# Power_3Escon_board_v2.net
KiCad netlist of a schematic drawn in EAGLE
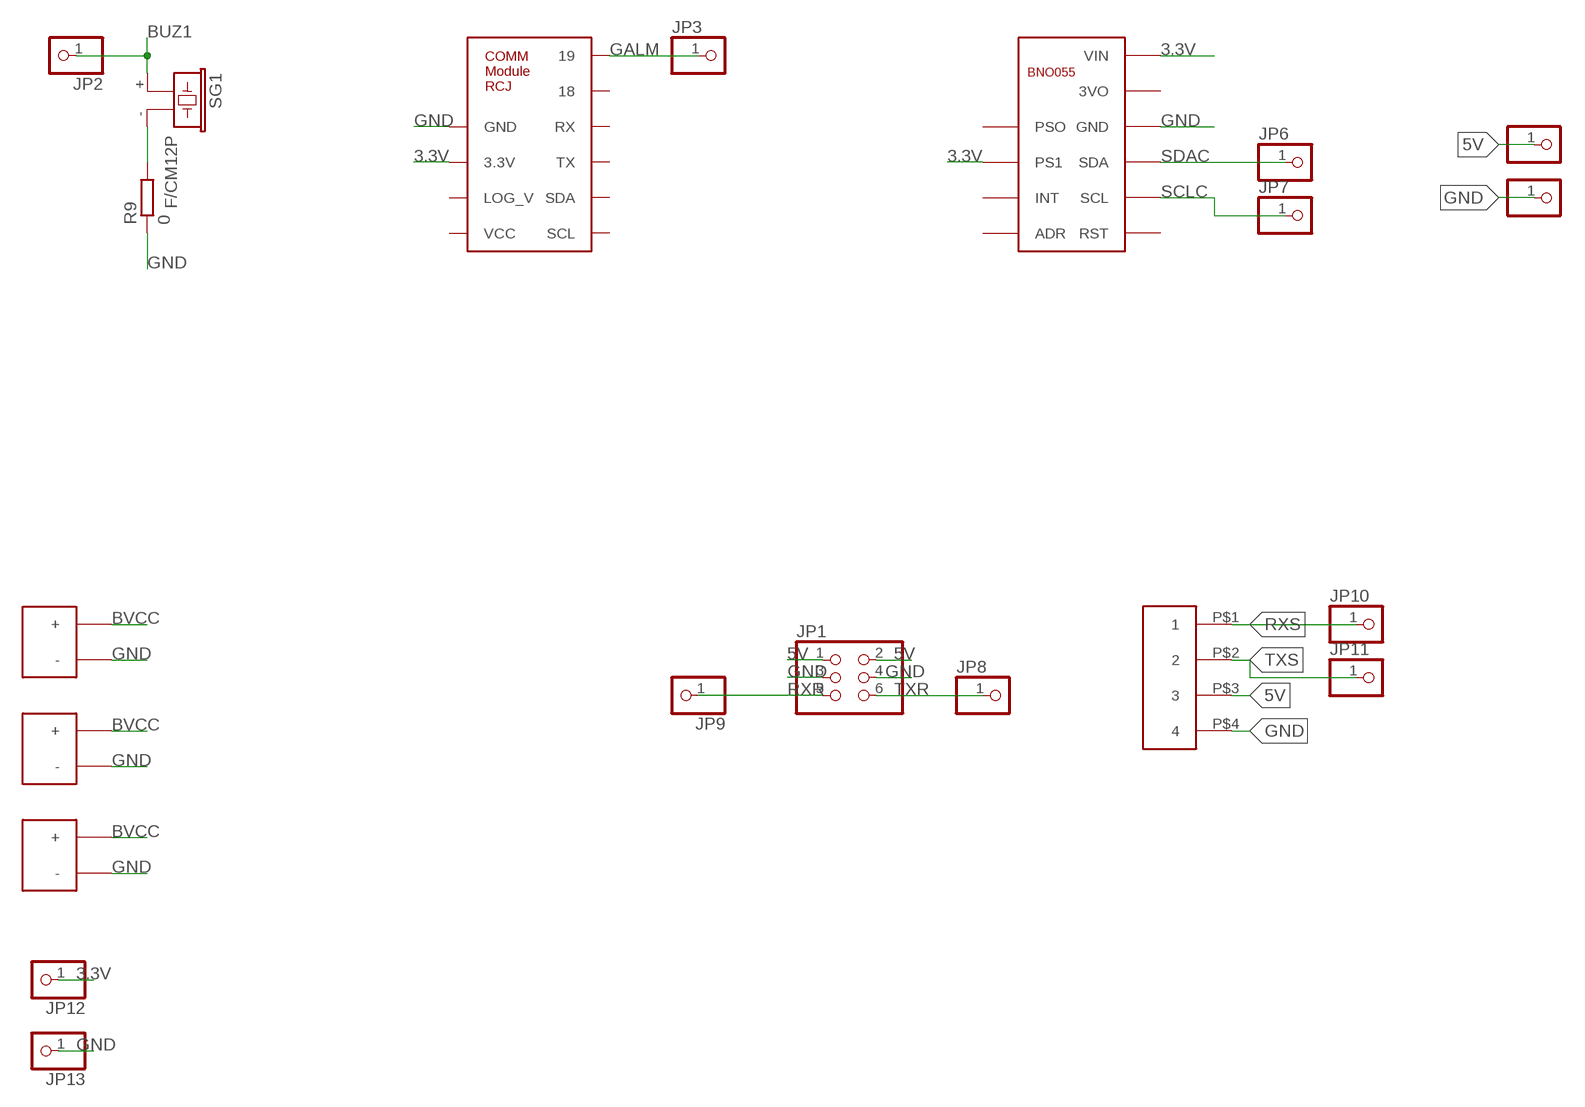
[diagram p0: schematic, sheet 1, part 1 of 3]
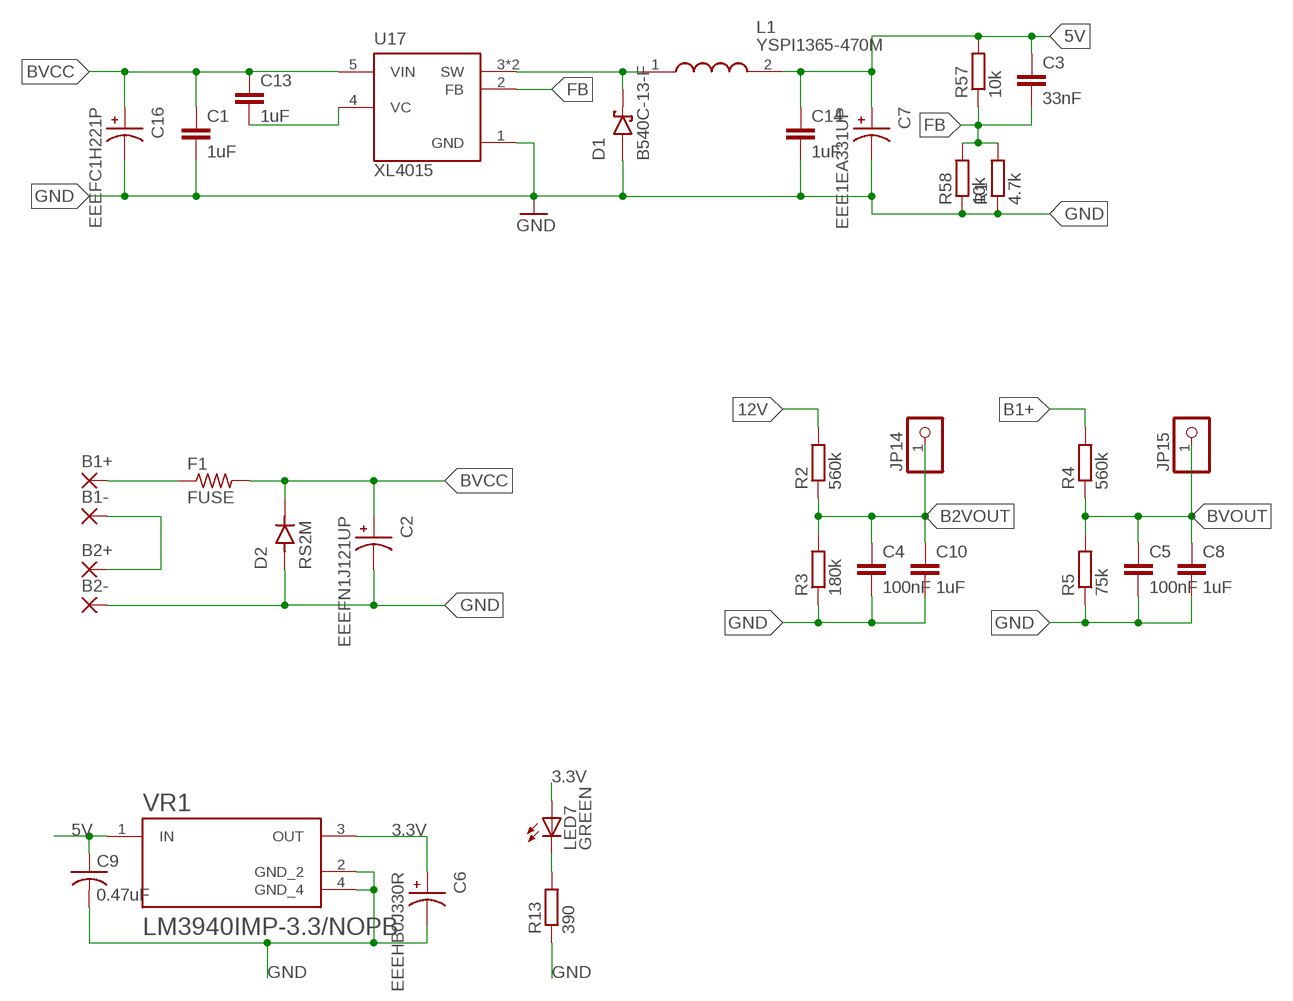
[diagram p1: schematic, sheet 1, part 2 of 3]
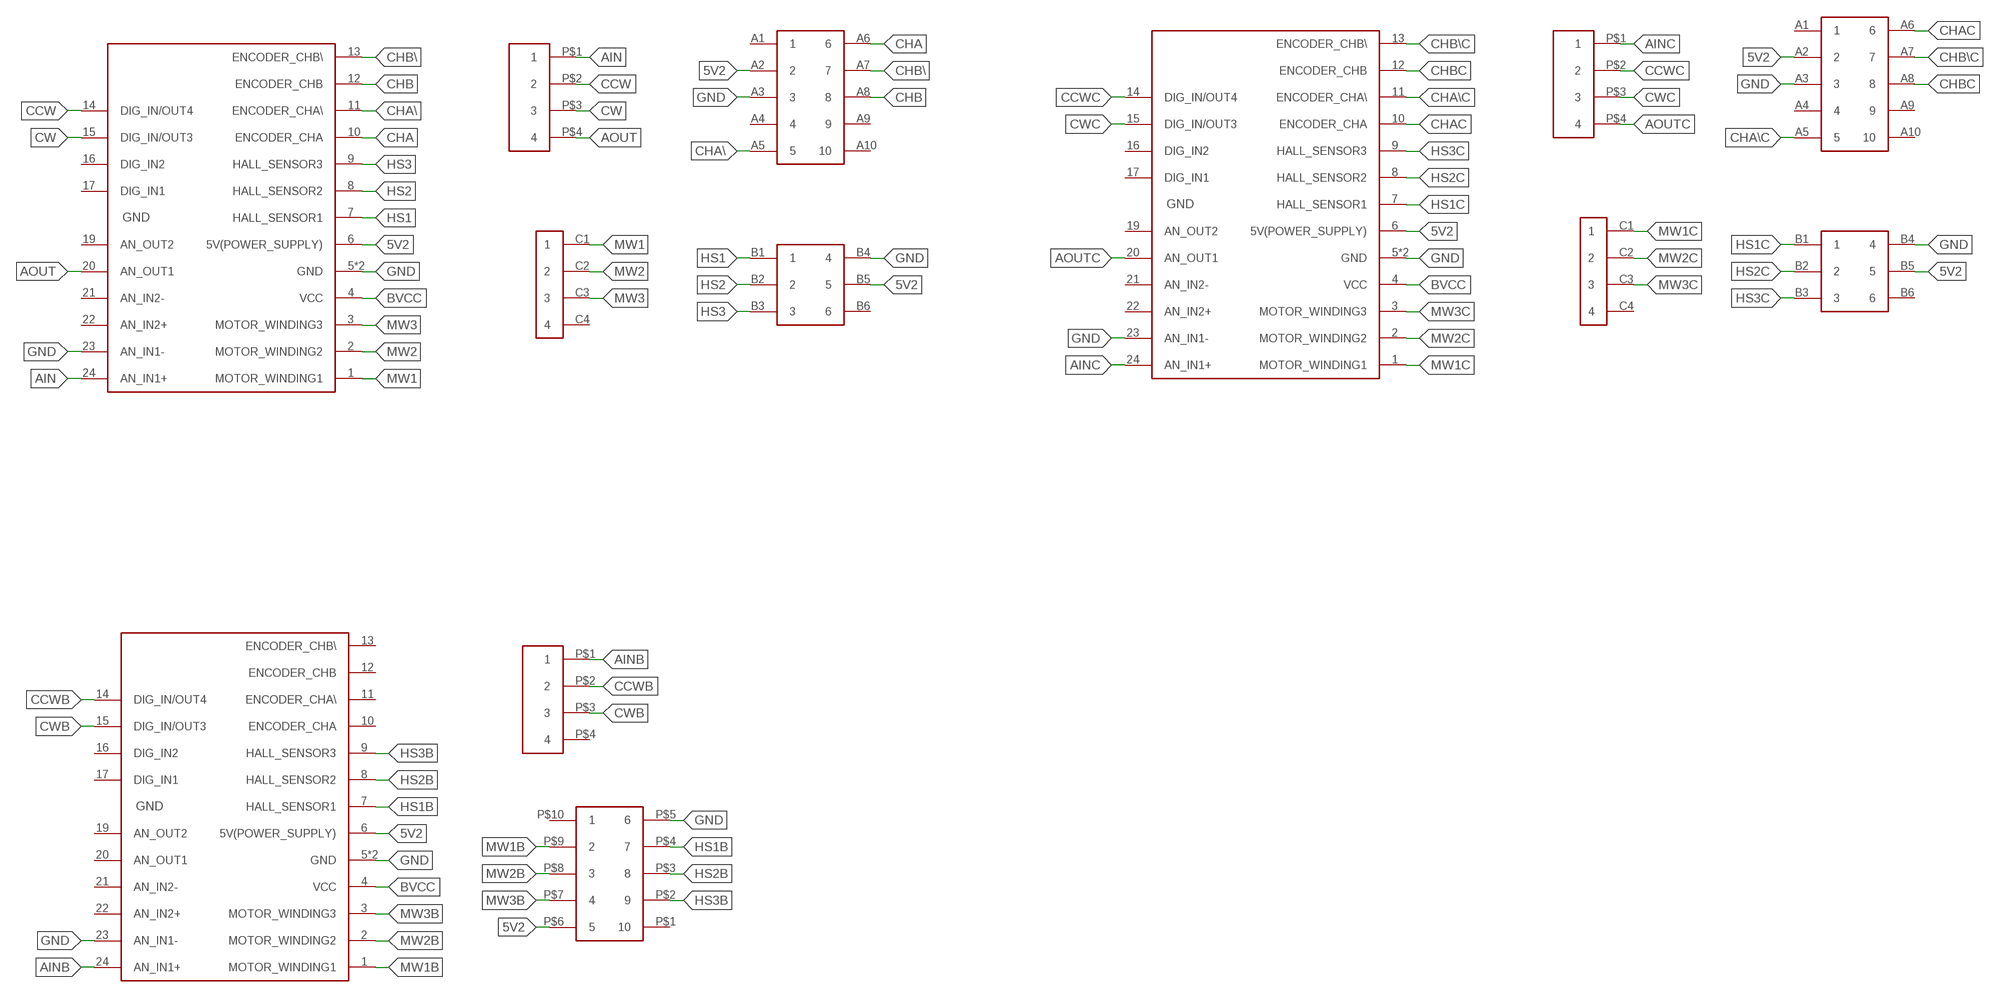
[diagram p2: schematic, sheet 1, part 3 of 3]

(export (version "E")
  (design (tool "Eeschema 10.0.6"))
  (components
    (comp (ref "B1+")
      (value "3,81/1,4")
      (footprint "eagle-import:3,81_1,4")
      (libsource (lib "eagle-import") (part "3,81/1,4"))
    )
    (comp (ref "B1-")
      (value "3,81/1,4")
      (footprint "eagle-import:3,81_1,4")
      (libsource (lib "eagle-import") (part "3,81/1,4"))
    )
    (comp (ref "B2+")
      (value "3,81/1,4")
      (footprint "eagle-import:3,81_1,4")
      (libsource (lib "eagle-import") (part "3,81/1,4"))
    )
    (comp (ref "B2-")
      (value "3,81/1,4")
      (footprint "eagle-import:3,81_1,4")
      (libsource (lib "eagle-import") (part "3,81/1,4"))
    )
    (comp (ref "C1")
      (value "1uF")
      (footprint "eagle-import:C0603")
      (libsource (lib "eagle-import") (part "C-EUC0603"))
    )
    (comp (ref "C2")
      (value "EEEFN1J121UP")
      (footprint "eagle-import:CAP_EEEFN1J121UP")
      (fields (field (name "MF") "Panasonic Electronic Components") (field (name "MP") "EEE-FN1J121UP"))
      (libsource (lib "eagle-import") (part "EEEFN1J121UP"))
    )
    (comp (ref "C3")
      (value "33nF")
      (footprint "eagle-import:C0603")
      (libsource (lib "eagle-import") (part "C-EUC0603"))
    )
    (comp (ref "C4")
      (value "100nF")
      (footprint "eagle-import:C0603")
      (libsource (lib "eagle-import") (part "C-EUC0603"))
    )
    (comp (ref "C5")
      (value "100nF")
      (footprint "eagle-import:C0603")
      (libsource (lib "eagle-import") (part "C-EUC0603"))
    )
    (comp (ref "C6")
      (value "EEEHB0J330R")
      (footprint "eagle-import:CAP_EEEHB0J330R")
      (fields (field (name "MF") "Panasonic") (field (name "MP") "EEE-HB0J330R"))
      (libsource (lib "eagle-import") (part "EEEHB0J330R"))
    )
    (comp (ref "C7")
      (value "EEE1EA331UP")
      (footprint "eagle-import:CAP_EEE1EA331UP")
      (fields (field (name "MF") "Panasonic"))
      (libsource (lib "eagle-import") (part "EEE1EA331UP"))
    )
    (comp (ref "C8")
      (value "1uF")
      (footprint "eagle-import:C0603")
      (libsource (lib "eagle-import") (part "C-EUC0603"))
    )
    (comp (ref "C9")
      (value "0.47uF")
      (footprint "eagle-import:C0603")
      (libsource (lib "eagle-import") (part "C-USC0603"))
    )
    (comp (ref "C10")
      (value "1uF")
      (footprint "eagle-import:C0603")
      (libsource (lib "eagle-import") (part "C-EUC0603"))
    )
    (comp (ref "C13")
      (value "1uF")
      (footprint "eagle-import:C0603")
      (libsource (lib "eagle-import") (part "C-EUC0603"))
    )
    (comp (ref "C14")
      (value "1uF")
      (footprint "eagle-import:C0603")
      (libsource (lib "eagle-import") (part "C-EUC0603"))
    )
    (comp (ref "C16")
      (value "EEEFC1H221P")
      (footprint "eagle-import:CAP_EEEFC1H221P")
      (fields (field (name "MF") "Panasonic"))
      (libsource (lib "eagle-import") (part "EEEFC1H221P"))
    )
    (comp (ref "D1")
      (value "B540C-13-F")
      (footprint "eagle-import:DIOM6959X245N")
      (fields (field (name "MF") "Diodes Inc."))
      (libsource (lib "eagle-import") (part "B540C-13-F"))
    )
    (comp (ref "D2")
      (value "RS2M")
      (footprint "eagle-import:DIOM4336X265N")
      (fields (field (name "MF") "Taiwan Semiconductor"))
      (libsource (lib "eagle-import") (part "RS2M"))
    )
    (comp (ref "F1")
      (value "FUSE")
      (footprint "eagle-import:R1206")
      (libsource (lib "eagle-import") (part "R-US_R1206"))
    )
    (comp (ref "JP1")
      (value "PINHD-2X3")
      (footprint "eagle-import:2X03")
      (libsource (lib "eagle-import") (part "PINHD-2X3"))
    )
    (comp (ref "JP2")
      (value "PINHD-1X1")
      (footprint "eagle-import:1X01")
      (libsource (lib "eagle-import") (part "PINHD-1X1"))
    )
    (comp (ref "JP3")
      (value "PINHD-1X1")
      (footprint "eagle-import:1X01")
      (libsource (lib "eagle-import") (part "PINHD-1X1"))
    )
    (comp (ref "JP4")
      (value "PINHD-1X1")
      (footprint "eagle-import:1X01")
      (libsource (lib "eagle-import") (part "PINHD-1X1"))
    )
    (comp (ref "JP5")
      (value "PINHD-1X1")
      (footprint "eagle-import:1X01")
      (libsource (lib "eagle-import") (part "PINHD-1X1"))
    )
    (comp (ref "JP6")
      (value "PINHD-1X1")
      (footprint "eagle-import:1X01")
      (libsource (lib "eagle-import") (part "PINHD-1X1"))
    )
    (comp (ref "JP7")
      (value "PINHD-1X1")
      (footprint "eagle-import:1X01")
      (libsource (lib "eagle-import") (part "PINHD-1X1"))
    )
    (comp (ref "JP8")
      (value "PINHD-1X1")
      (footprint "eagle-import:1X01")
      (libsource (lib "eagle-import") (part "PINHD-1X1"))
    )
    (comp (ref "JP9")
      (value "PINHD-1X1")
      (footprint "eagle-import:1X01")
      (libsource (lib "eagle-import") (part "PINHD-1X1"))
    )
    (comp (ref "JP10")
      (value "PINHD-1X1")
      (footprint "eagle-import:1X01")
      (libsource (lib "eagle-import") (part "PINHD-1X1"))
    )
    (comp (ref "JP11")
      (value "PINHD-1X1")
      (footprint "eagle-import:1X01")
      (libsource (lib "eagle-import") (part "PINHD-1X1"))
    )
    (comp (ref "JP12")
      (value "PINHD-1X1")
      (footprint "eagle-import:1X01")
      (libsource (lib "eagle-import") (part "PINHD-1X1"))
    )
    (comp (ref "JP13")
      (value "PINHD-1X1")
      (footprint "eagle-import:1X01")
      (libsource (lib "eagle-import") (part "PINHD-1X1"))
    )
    (comp (ref "JP14")
      (value "PINHD-1X1")
      (footprint "eagle-import:1X01")
      (libsource (lib "eagle-import") (part "PINHD-1X1"))
    )
    (comp (ref "JP15")
      (value "PINHD-1X1")
      (footprint "eagle-import:1X01")
      (libsource (lib "eagle-import") (part "PINHD-1X1"))
    )
    (comp (ref "L1")
      (value "YSPI1365-470M")
      (footprint "eagle-import:INDPM138126X650N")
      (libsource (lib "eagle-import") (part "YSPI1365-470M"))
    )
    (comp (ref "LED7")
      (value "GREEN")
      (footprint "eagle-import:CHIPLED_0603")
      (libsource (lib "eagle-import") (part "LEDCHIPLED_0603"))
    )
    (comp (ref "R1")
      (value "4.7k")
      (footprint "eagle-import:R0603")
      (libsource (lib "eagle-import") (part "R-EU_R0603"))
    )
    (comp (ref "R2")
      (value "560k")
      (footprint "eagle-import:R0603")
      (libsource (lib "eagle-import") (part "R-EU_R0603"))
    )
    (comp (ref "R3")
      (value "180k")
      (footprint "eagle-import:R0603")
      (libsource (lib "eagle-import") (part "R-EU_R0603"))
    )
    (comp (ref "R4")
      (value "560k")
      (footprint "eagle-import:R0603")
      (libsource (lib "eagle-import") (part "R-EU_R0603"))
    )
    (comp (ref "R5")
      (value "75k")
      (footprint "eagle-import:R0603")
      (libsource (lib "eagle-import") (part "R-EU_R0603"))
    )
    (comp (ref "R9")
      (value "0")
      (footprint "eagle-import:R0603")
      (libsource (lib "eagle-import") (part "R-EU_R0603"))
    )
    (comp (ref "R13")
      (value "390")
      (footprint "eagle-import:R0603")
      (libsource (lib "eagle-import") (part "R-EU_R0603"))
    )
    (comp (ref "R57")
      (value "10k")
      (footprint "eagle-import:R0603")
      (libsource (lib "eagle-import") (part "R-EU_R0603"))
    )
    (comp (ref "R58")
      (value "10k")
      (footprint "eagle-import:R0603")
      (libsource (lib "eagle-import") (part "R-EU_R0603"))
    )
    (comp (ref "SG1")
      (value "F/CM12P")
      (footprint "eagle-import:F_CM12P")
      (libsource (lib "eagle-import") (part "F/CM12P"))
    )
    (comp (ref "U$1")
      (value "ESCON24/224/2")
      (footprint "eagle-import:ESCON24_2")
      (libsource (lib "eagle-import") (part "ESCON24/224/2"))
    )
    (comp (ref "U$2")
      (value "GAL_MODULE")
      (footprint "eagle-import:GAL_MODULE")
      (libsource (lib "eagle-import") (part "GAL_MODULE"))
    )
    (comp (ref "U$3")
      (value "BNO055")
      (footprint "eagle-import:BNO055")
      (libsource (lib "eagle-import") (part "BNO055"))
    )
    (comp (ref "U$4")
      (value "280378-2CONNECTOR")
      (footprint "eagle-import:280378-2CONNECTOR")
      (libsource (lib "eagle-import") (part "280378-2CONNECTOR"))
    )
    (comp (ref "U$5")
      (value "PIN2.54-2X5")
      (footprint "eagle-import:PIN2.54-2X5")
      (libsource (lib "eagle-import") (part "PIN2.54-2X5"))
    )
    (comp (ref "U$6")
      (value "MX-44914-0601")
      (footprint "eagle-import:MX-44914-0601")
      (libsource (lib "eagle-import") (part "MX-44914-0601"))
    )
    (comp (ref "U$7")
      (value "MX5566")
      (footprint "eagle-import:MX5566")
      (libsource (lib "eagle-import") (part "MX5566"))
    )
    (comp (ref "U$10")
      (value "ESCON24/224/2")
      (footprint "eagle-import:ESCON24_2")
      (libsource (lib "eagle-import") (part "ESCON24/224/2"))
    )
    (comp (ref "U$13")
      (value "280378-2CONNECTOR")
      (footprint "eagle-import:280378-2CONNECTOR")
      (libsource (lib "eagle-import") (part "280378-2CONNECTOR"))
    )
    (comp (ref "U$14")
      (value "2,5MSF10")
      (footprint "eagle-import:2,5MSF10")
      (libsource (lib "eagle-import") (part "2,5MSF10"))
    )
    (comp (ref "U$15")
      (value "ESCON24/224/2")
      (footprint "eagle-import:ESCON24_2")
      (libsource (lib "eagle-import") (part "ESCON24/224/2"))
    )
    (comp (ref "U$16")
      (value "280378-2CONNECTOR")
      (footprint "eagle-import:280378-2CONNECTOR")
      (libsource (lib "eagle-import") (part "280378-2CONNECTOR"))
    )
    (comp (ref "U$17")
      (value "PIN2.54-2X5")
      (footprint "eagle-import:PIN2.54-2X5")
      (libsource (lib "eagle-import") (part "PIN2.54-2X5"))
    )
    (comp (ref "U$18")
      (value "MX-44914-0601")
      (footprint "eagle-import:MX-44914-0601")
      (libsource (lib "eagle-import") (part "MX-44914-0601"))
    )
    (comp (ref "U$19")
      (value "MX5566")
      (footprint "eagle-import:MX5566")
      (libsource (lib "eagle-import") (part "MX5566"))
    )
    (comp (ref "U$22")
      (value "280378-2CONNECTOR")
      (footprint "eagle-import:280378-2CONNECTOR")
      (libsource (lib "eagle-import") (part "280378-2CONNECTOR"))
    )
    (comp (ref "U$23")
      (value "SVORKOVNICA3.5_P2")
      (footprint "eagle-import:SVORKOVNICA3.5")
      (libsource (lib "eagle-import") (part "SVORKOVNICA3.5_P2"))
    )
    (comp (ref "U$24")
      (value "SVORKOVNICA3.5_P2")
      (footprint "eagle-import:SVORKOVNICA3.5")
      (libsource (lib "eagle-import") (part "SVORKOVNICA3.5_P2"))
    )
    (comp (ref "U$25")
      (value "SVORKOVNICA3.5_P2")
      (footprint "eagle-import:SVORKOVNICA3.5")
      (libsource (lib "eagle-import") (part "SVORKOVNICA3.5_P2"))
    )
    (comp (ref "U17")
      (value "XL4015")
      (footprint "eagle-import:CONV_XL4015")
      (fields (field (name "MF") "XLSEMI"))
      (libsource (lib "eagle-import") (part "XL4015"))
    )
    (comp (ref "VR1")
      (value "LM3940IMP-3.3/NOPB")
      (footprint "eagle-import:VREG_LM3940IMP-3.3_NOPB")
      (fields (field (name "MF") "Texas Instruments") (field (name "MP") "LM3940IMP-3.3"))
      (libsource (lib "eagle-import") (part "LM3940IMP-3.3/NOPB"))
    )
  )
  (nets
    (net (code "1") (name "/3.3V") (class "Default")
      (node (ref "C6") (pin "1") (pinfunction "1_1") (pintype "passive"))
      (node (ref "JP12") (pin "1") (pinfunction "1_1") (pintype "passive"))
      (node (ref "LED7") (pin "A") (pinfunction "A_A") (pintype "passive"))
      (node (ref "U$2") (pin "3.3V") (pinfunction "3.3V_3.3V") (pintype "bidirectional"))
      (node (ref "U$3") (pin "PS1") (pinfunction "PS1_PS1") (pintype "bidirectional"))
      (node (ref "U$3") (pin "VIN") (pinfunction "VIN_VIN") (pintype "bidirectional"))
      (node (ref "VR1") (pin "3") (pinfunction "OUT_3") (pintype "output"))
    )
    (net (code "2") (name "/BUZ1") (class "Default")
      (node (ref "JP2") (pin "1") (pinfunction "1_1") (pintype "passive"))
      (node (ref "SG1") (pin "+") (pinfunction "1_+") (pintype "passive"))
    )
    (net (code "3") (name "/GALM") (class "Default")
      (node (ref "JP3") (pin "1") (pinfunction "1_1") (pintype "passive"))
      (node (ref "U$2") (pin "19") (pinfunction "19_19") (pintype "bidirectional"))
    )
    (net (code "4") (name "/RXR") (class "Default")
      (node (ref "JP1") (pin "5") (pinfunction "5_5") (pintype "passive"))
      (node (ref "JP9") (pin "1") (pinfunction "1_1") (pintype "passive"))
    )
    (net (code "5") (name "/SCLC") (class "Default")
      (node (ref "JP7") (pin "1") (pinfunction "1_1") (pintype "passive"))
      (node (ref "U$3") (pin "SCL") (pinfunction "SCL_SCL") (pintype "bidirectional"))
    )
    (net (code "6") (name "/SDAC") (class "Default")
      (node (ref "JP6") (pin "1") (pinfunction "1_1") (pintype "passive"))
      (node (ref "U$3") (pin "SDA") (pinfunction "SDA_SDA") (pintype "bidirectional"))
    )
    (net (code "7") (name "/TXR") (class "Default")
      (node (ref "JP1") (pin "6") (pinfunction "6_6") (pintype "passive"))
      (node (ref "JP8") (pin "1") (pinfunction "1_1") (pintype "passive"))
    )
    (net (code "8") (name "5V") (class "Default")
      (node (ref "C14") (pin "1") (pinfunction "1_1") (pintype "passive"))
      (node (ref "C3") (pin "1") (pinfunction "1_1") (pintype "passive"))
      (node (ref "C7") (pin "1") (pinfunction "1_1") (pintype "passive"))
      (node (ref "C9") (pin "1") (pinfunction "1_1") (pintype "passive"))
      (node (ref "JP1") (pin "1") (pinfunction "1_1") (pintype "passive"))
      (node (ref "JP1") (pin "2") (pinfunction "2_2") (pintype "passive"))
      (node (ref "JP4") (pin "1") (pinfunction "1_1") (pintype "passive"))
      (node (ref "L1") (pin "2") (pinfunction "2_2") (pintype "bidirectional"))
      (node (ref "R57") (pin "2") (pinfunction "2_2") (pintype "passive"))
      (node (ref "U$22") (pin "P$3") (pinfunction "3_P$3") (pintype "bidirectional"))
      (node (ref "VR1") (pin "1") (pinfunction "IN_1") (pintype "input"))
    )
    (net (code "9") (name "5V2") (class "Default")
      (node (ref "U$1") (pin "6") (pinfunction "5V(POWER_SUPPLY)_6") (pintype "bidirectional"))
      (node (ref "U$10") (pin "6") (pinfunction "5V(POWER_SUPPLY)_6") (pintype "bidirectional"))
      (node (ref "U$14") (pin "P$6") (pinfunction "5_P$6") (pintype "bidirectional"))
      (node (ref "U$15") (pin "6") (pinfunction "5V(POWER_SUPPLY)_6") (pintype "bidirectional"))
      (node (ref "U$17") (pin "A2") (pinfunction "2_A2") (pintype "bidirectional"))
      (node (ref "U$18") (pin "B5") (pinfunction "5_B5") (pintype "bidirectional"))
      (node (ref "U$5") (pin "A2") (pinfunction "2_A2") (pintype "bidirectional"))
      (node (ref "U$6") (pin "B5") (pinfunction "5_B5") (pintype "bidirectional"))
    )
    (net (code "10") (name "12V") (class "Default")
      (node (ref "B1-") (pin "1") (pinfunction "P_1") (pintype "passive"))
      (node (ref "B2+") (pin "1") (pinfunction "P_1") (pintype "passive"))
      (node (ref "R2") (pin "2") (pinfunction "2_2") (pintype "passive"))
    )
    (net (code "11") (name "AIN") (class "Default")
      (node (ref "U$1") (pin "24") (pinfunction "AN_IN1+_24") (pintype "bidirectional"))
      (node (ref "U$4") (pin "P$1") (pinfunction "1_P$1") (pintype "bidirectional"))
    )
    (net (code "12") (name "AINB") (class "Default")
      (node (ref "U$10") (pin "24") (pinfunction "AN_IN1+_24") (pintype "bidirectional"))
      (node (ref "U$13") (pin "P$1") (pinfunction "1_P$1") (pintype "bidirectional"))
    )
    (net (code "13") (name "AINC") (class "Default")
      (node (ref "U$15") (pin "24") (pinfunction "AN_IN1+_24") (pintype "bidirectional"))
      (node (ref "U$16") (pin "P$1") (pinfunction "1_P$1") (pintype "bidirectional"))
    )
    (net (code "14") (name "AOUT") (class "Default")
      (node (ref "U$1") (pin "20") (pinfunction "AN_OUT1_20") (pintype "bidirectional"))
      (node (ref "U$4") (pin "P$4") (pinfunction "4_P$4") (pintype "bidirectional"))
    )
    (net (code "15") (name "AOUTC") (class "Default")
      (node (ref "U$15") (pin "20") (pinfunction "AN_OUT1_20") (pintype "bidirectional"))
      (node (ref "U$16") (pin "P$4") (pinfunction "4_P$4") (pintype "bidirectional"))
    )
    (net (code "16") (name "B1+") (class "Default")
      (node (ref "B1+") (pin "1") (pinfunction "P_1") (pintype "passive"))
      (node (ref "F1") (pin "1") (pinfunction "1_1") (pintype "passive"))
      (node (ref "R4") (pin "2") (pinfunction "2_2") (pintype "passive"))
    )
    (net (code "17") (name "B2VOUT") (class "Default")
      (node (ref "C10") (pin "1") (pinfunction "1_1") (pintype "passive"))
      (node (ref "C4") (pin "1") (pinfunction "1_1") (pintype "passive"))
      (node (ref "JP14") (pin "1") (pinfunction "1_1") (pintype "passive"))
      (node (ref "R2") (pin "1") (pinfunction "1_1") (pintype "passive"))
      (node (ref "R3") (pin "2") (pinfunction "2_2") (pintype "passive"))
    )
    (net (code "18") (name "BVCC") (class "Default")
      (node (ref "C1") (pin "1") (pinfunction "1_1") (pintype "passive"))
      (node (ref "C13") (pin "1") (pinfunction "1_1") (pintype "passive"))
      (node (ref "C16") (pin "1") (pinfunction "1_1") (pintype "passive"))
      (node (ref "C2") (pin "1") (pinfunction "1_1") (pintype "passive"))
      (node (ref "D2") (pin "C") (pinfunction "K_C") (pintype "passive"))
      (node (ref "F1") (pin "2") (pinfunction "2_2") (pintype "passive"))
      (node (ref "U$1") (pin "4") (pinfunction "VCC_4") (pintype "bidirectional"))
      (node (ref "U$10") (pin "4") (pinfunction "VCC_4") (pintype "bidirectional"))
      (node (ref "U$15") (pin "4") (pinfunction "VCC_4") (pintype "bidirectional"))
      (node (ref "U$23") (pin "P$1") (pinfunction "+_P$1") (pintype "bidirectional"))
      (node (ref "U$24") (pin "P$1") (pinfunction "+_P$1") (pintype "bidirectional"))
      (node (ref "U$25") (pin "P$1") (pinfunction "+_P$1") (pintype "bidirectional"))
      (node (ref "U17") (pin "5") (pinfunction "VIN_5") (pintype "input"))
    )
    (net (code "19") (name "BVOUT") (class "Default")
      (node (ref "C5") (pin "1") (pinfunction "1_1") (pintype "passive"))
      (node (ref "C8") (pin "1") (pinfunction "1_1") (pintype "passive"))
      (node (ref "JP15") (pin "1") (pinfunction "1_1") (pintype "passive"))
      (node (ref "R4") (pin "1") (pinfunction "1_1") (pintype "passive"))
      (node (ref "R5") (pin "2") (pinfunction "2_2") (pintype "passive"))
    )
    (net (code "20") (name "CCW") (class "Default")
      (node (ref "U$1") (pin "14") (pinfunction "DIG_IN/OUT4_14") (pintype "bidirectional"))
      (node (ref "U$4") (pin "P$2") (pinfunction "2_P$2") (pintype "bidirectional"))
    )
    (net (code "21") (name "CCWB") (class "Default")
      (node (ref "U$10") (pin "14") (pinfunction "DIG_IN/OUT4_14") (pintype "bidirectional"))
      (node (ref "U$13") (pin "P$2") (pinfunction "2_P$2") (pintype "bidirectional"))
    )
    (net (code "22") (name "CCWC") (class "Default")
      (node (ref "U$15") (pin "14") (pinfunction "DIG_IN/OUT4_14") (pintype "bidirectional"))
      (node (ref "U$16") (pin "P$2") (pinfunction "2_P$2") (pintype "bidirectional"))
    )
    (net (code "23") (name "CHA") (class "Default")
      (node (ref "U$1") (pin "10") (pinfunction "ENCODER_CHA_10") (pintype "bidirectional"))
      (node (ref "U$5") (pin "A6") (pinfunction "6_A6") (pintype "bidirectional"))
    )
    (net (code "24") (name "CHAC") (class "Default")
      (node (ref "U$15") (pin "10") (pinfunction "ENCODER_CHA_10") (pintype "bidirectional"))
      (node (ref "U$17") (pin "A6") (pinfunction "6_A6") (pintype "bidirectional"))
    )
    (net (code "25") (name "CHA\\\\") (class "Default")
      (node (ref "U$1") (pin "11") (pinfunction "ENCODER_CHA\\\\_11") (pintype "bidirectional"))
      (node (ref "U$5") (pin "A5") (pinfunction "5_A5") (pintype "bidirectional"))
    )
    (net (code "26") (name "CHA\\\\C") (class "Default")
      (node (ref "U$15") (pin "11") (pinfunction "ENCODER_CHA\\\\_11") (pintype "bidirectional"))
      (node (ref "U$17") (pin "A5") (pinfunction "5_A5") (pintype "bidirectional"))
    )
    (net (code "27") (name "CHB") (class "Default")
      (node (ref "U$1") (pin "12") (pinfunction "ENCODER_CHB_12") (pintype "bidirectional"))
      (node (ref "U$5") (pin "A8") (pinfunction "8_A8") (pintype "bidirectional"))
    )
    (net (code "28") (name "CHBC") (class "Default")
      (node (ref "U$15") (pin "12") (pinfunction "ENCODER_CHB_12") (pintype "bidirectional"))
      (node (ref "U$17") (pin "A8") (pinfunction "8_A8") (pintype "bidirectional"))
    )
    (net (code "29") (name "CHB\\\\") (class "Default")
      (node (ref "U$1") (pin "13") (pinfunction "ENCODER_CHB\\\\_13") (pintype "bidirectional"))
      (node (ref "U$5") (pin "A7") (pinfunction "7_A7") (pintype "bidirectional"))
    )
    (net (code "30") (name "CHB\\\\C") (class "Default")
      (node (ref "U$15") (pin "13") (pinfunction "ENCODER_CHB\\\\_13") (pintype "bidirectional"))
      (node (ref "U$17") (pin "A7") (pinfunction "7_A7") (pintype "bidirectional"))
    )
    (net (code "31") (name "CW") (class "Default")
      (node (ref "U$1") (pin "15") (pinfunction "DIG_IN/OUT3_15") (pintype "bidirectional"))
      (node (ref "U$4") (pin "P$3") (pinfunction "3_P$3") (pintype "bidirectional"))
    )
    (net (code "32") (name "CWB") (class "Default")
      (node (ref "U$10") (pin "15") (pinfunction "DIG_IN/OUT3_15") (pintype "bidirectional"))
      (node (ref "U$13") (pin "P$3") (pinfunction "3_P$3") (pintype "bidirectional"))
    )
    (net (code "33") (name "CWC") (class "Default")
      (node (ref "U$15") (pin "15") (pinfunction "DIG_IN/OUT3_15") (pintype "bidirectional"))
      (node (ref "U$16") (pin "P$3") (pinfunction "3_P$3") (pintype "bidirectional"))
    )
    (net (code "34") (name "FB") (class "Default")
      (node (ref "C3") (pin "2") (pinfunction "2_2") (pintype "passive"))
      (node (ref "R1") (pin "2") (pinfunction "2_2") (pintype "passive"))
      (node (ref "R57") (pin "1") (pinfunction "1_1") (pintype "passive"))
      (node (ref "R58") (pin "2") (pinfunction "2_2") (pintype "passive"))
      (node (ref "U17") (pin "2") (pinfunction "FB_2") (pintype "input"))
    )
    (net (code "35") (name "GND") (class "Default")
      (node (ref "B2-") (pin "1") (pinfunction "P_1") (pintype "passive"))
      (node (ref "C1") (pin "2") (pinfunction "2_2") (pintype "passive"))
      (node (ref "C10") (pin "2") (pinfunction "2_2") (pintype "passive"))
      (node (ref "C14") (pin "2") (pinfunction "2_2") (pintype "passive"))
      (node (ref "C16") (pin "2") (pinfunction "2_2") (pintype "passive"))
      (node (ref "C2") (pin "2") (pinfunction "2_2") (pintype "passive"))
      (node (ref "C4") (pin "2") (pinfunction "2_2") (pintype "passive"))
      (node (ref "C5") (pin "2") (pinfunction "2_2") (pintype "passive"))
      (node (ref "C6") (pin "2") (pinfunction "2_2") (pintype "passive"))
      (node (ref "C7") (pin "2") (pinfunction "2_2") (pintype "passive"))
      (node (ref "C8") (pin "2") (pinfunction "2_2") (pintype "passive"))
      (node (ref "C9") (pin "2") (pinfunction "2_2") (pintype "passive"))
      (node (ref "D1") (pin "A") (pinfunction "A_A") (pintype "passive"))
      (node (ref "D2") (pin "A") (pinfunction "A_A") (pintype "passive"))
      (node (ref "JP1") (pin "3") (pinfunction "3_3") (pintype "passive"))
      (node (ref "JP1") (pin "4") (pinfunction "4_4") (pintype "passive"))
      (node (ref "JP13") (pin "1") (pinfunction "1_1") (pintype "passive"))
      (node (ref "JP5") (pin "1") (pinfunction "1_1") (pintype "passive"))
      (node (ref "R1") (pin "1") (pinfunction "1_1") (pintype "passive"))
      (node (ref "R13") (pin "1") (pinfunction "1_1") (pintype "passive"))
      (node (ref "R3") (pin "1") (pinfunction "1_1") (pintype "passive"))
      (node (ref "R5") (pin "1") (pinfunction "1_1") (pintype "passive"))
      (node (ref "R58") (pin "1") (pinfunction "1_1") (pintype "passive"))
      (node (ref "R9") (pin "1") (pinfunction "1_1") (pintype "passive"))
      (node (ref "U$1") (pin "18") (pinfunction "GND_18") (pintype "bidirectional"))
      (node (ref "U$1") (pin "23") (pinfunction "AN_IN1-_23") (pintype "bidirectional"))
      (node (ref "U$1") (pin "5") (pinfunction "GND_5") (pintype "bidirectional"))
      (node (ref "U$10") (pin "18") (pinfunction "GND_18") (pintype "bidirectional"))
      (node (ref "U$10") (pin "23") (pinfunction "AN_IN1-_23") (pintype "bidirectional"))
      (node (ref "U$10") (pin "5") (pinfunction "GND_5") (pintype "bidirectional"))
      (node (ref "U$14") (pin "P$5") (pinfunction "6_P$5") (pintype "bidirectional"))
      (node (ref "U$15") (pin "18") (pinfunction "GND_18") (pintype "bidirectional"))
      (node (ref "U$15") (pin "23") (pinfunction "AN_IN1-_23") (pintype "bidirectional"))
      (node (ref "U$15") (pin "5") (pinfunction "GND_5") (pintype "bidirectional"))
      (node (ref "U$17") (pin "A3") (pinfunction "3_A3") (pintype "bidirectional"))
      (node (ref "U$18") (pin "B4") (pinfunction "4_B4") (pintype "bidirectional"))
      (node (ref "U$2") (pin "GND") (pinfunction "GND_GND") (pintype "bidirectional"))
      (node (ref "U$22") (pin "P$4") (pinfunction "4_P$4") (pintype "bidirectional"))
      (node (ref "U$23") (pin "P$2") (pinfunction "-_P$2") (pintype "bidirectional"))
      (node (ref "U$24") (pin "P$2") (pinfunction "-_P$2") (pintype "bidirectional"))
      (node (ref "U$25") (pin "P$2") (pinfunction "-_P$2") (pintype "bidirectional"))
      (node (ref "U$3") (pin "GND") (pinfunction "GND_GND") (pintype "bidirectional"))
      (node (ref "U$5") (pin "A3") (pinfunction "3_A3") (pintype "bidirectional"))
      (node (ref "U$6") (pin "B4") (pinfunction "4_B4") (pintype "bidirectional"))
      (node (ref "U17") (pin "1") (pinfunction "GND_1") (pintype "power_in"))
      (node (ref "VR1") (pin "2") (pinfunction "GND_2_2") (pintype "power_in"))
      (node (ref "VR1") (pin "4") (pinfunction "GND_4_4") (pintype "power_in"))
    )
    (net (code "36") (name "HS1") (class "Default")
      (node (ref "U$1") (pin "7") (pinfunction "HALL_SENSOR1_7") (pintype "bidirectional"))
      (node (ref "U$6") (pin "B1") (pinfunction "1_B1") (pintype "bidirectional"))
    )
    (net (code "37") (name "HS1B") (class "Default")
      (node (ref "U$10") (pin "7") (pinfunction "HALL_SENSOR1_7") (pintype "bidirectional"))
      (node (ref "U$14") (pin "P$4") (pinfunction "7_P$4") (pintype "bidirectional"))
    )
    (net (code "38") (name "HS1C") (class "Default")
      (node (ref "U$15") (pin "7") (pinfunction "HALL_SENSOR1_7") (pintype "bidirectional"))
      (node (ref "U$18") (pin "B1") (pinfunction "1_B1") (pintype "bidirectional"))
    )
    (net (code "39") (name "HS2") (class "Default")
      (node (ref "U$1") (pin "8") (pinfunction "HALL_SENSOR2_8") (pintype "bidirectional"))
      (node (ref "U$6") (pin "B2") (pinfunction "2_B2") (pintype "bidirectional"))
    )
    (net (code "40") (name "HS2B") (class "Default")
      (node (ref "U$10") (pin "8") (pinfunction "HALL_SENSOR2_8") (pintype "bidirectional"))
      (node (ref "U$14") (pin "P$3") (pinfunction "8_P$3") (pintype "bidirectional"))
    )
    (net (code "41") (name "HS2C") (class "Default")
      (node (ref "U$15") (pin "8") (pinfunction "HALL_SENSOR2_8") (pintype "bidirectional"))
      (node (ref "U$18") (pin "B2") (pinfunction "2_B2") (pintype "bidirectional"))
    )
    (net (code "42") (name "HS3") (class "Default")
      (node (ref "U$1") (pin "9") (pinfunction "HALL_SENSOR3_9") (pintype "bidirectional"))
      (node (ref "U$6") (pin "B3") (pinfunction "3_B3") (pintype "bidirectional"))
    )
    (net (code "43") (name "HS3B") (class "Default")
      (node (ref "U$10") (pin "9") (pinfunction "HALL_SENSOR3_9") (pintype "bidirectional"))
      (node (ref "U$14") (pin "P$2") (pinfunction "9_P$2") (pintype "bidirectional"))
    )
    (net (code "44") (name "HS3C") (class "Default")
      (node (ref "U$15") (pin "9") (pinfunction "HALL_SENSOR3_9") (pintype "bidirectional"))
      (node (ref "U$18") (pin "B3") (pinfunction "3_B3") (pintype "bidirectional"))
    )
    (net (code "45") (name "MW1") (class "Default")
      (node (ref "U$1") (pin "1") (pinfunction "MOTOR_WINDING1_1") (pintype "bidirectional"))
      (node (ref "U$7") (pin "C1") (pinfunction "1_C1") (pintype "bidirectional"))
    )
    (net (code "46") (name "MW1B") (class "Default")
      (node (ref "U$10") (pin "1") (pinfunction "MOTOR_WINDING1_1") (pintype "bidirectional"))
      (node (ref "U$14") (pin "P$9") (pinfunction "2_P$9") (pintype "bidirectional"))
    )
    (net (code "47") (name "MW1C") (class "Default")
      (node (ref "U$15") (pin "1") (pinfunction "MOTOR_WINDING1_1") (pintype "bidirectional"))
      (node (ref "U$19") (pin "C1") (pinfunction "1_C1") (pintype "bidirectional"))
    )
    (net (code "48") (name "MW2") (class "Default")
      (node (ref "U$1") (pin "2") (pinfunction "MOTOR_WINDING2_2") (pintype "bidirectional"))
      (node (ref "U$7") (pin "C2") (pinfunction "2_C2") (pintype "bidirectional"))
    )
    (net (code "49") (name "MW2B") (class "Default")
      (node (ref "U$10") (pin "2") (pinfunction "MOTOR_WINDING2_2") (pintype "bidirectional"))
      (node (ref "U$14") (pin "P$8") (pinfunction "3_P$8") (pintype "bidirectional"))
    )
    (net (code "50") (name "MW2C") (class "Default")
      (node (ref "U$15") (pin "2") (pinfunction "MOTOR_WINDING2_2") (pintype "bidirectional"))
      (node (ref "U$19") (pin "C2") (pinfunction "2_C2") (pintype "bidirectional"))
    )
    (net (code "51") (name "MW3") (class "Default")
      (node (ref "U$1") (pin "3") (pinfunction "MOTOR_WINDING3_3") (pintype "bidirectional"))
      (node (ref "U$7") (pin "C3") (pinfunction "3_C3") (pintype "bidirectional"))
    )
    (net (code "52") (name "MW3B") (class "Default")
      (node (ref "U$10") (pin "3") (pinfunction "MOTOR_WINDING3_3") (pintype "bidirectional"))
      (node (ref "U$14") (pin "P$7") (pinfunction "4_P$7") (pintype "bidirectional"))
    )
    (net (code "53") (name "MW3C") (class "Default")
      (node (ref "U$15") (pin "3") (pinfunction "MOTOR_WINDING3_3") (pintype "bidirectional"))
      (node (ref "U$19") (pin "C3") (pinfunction "3_C3") (pintype "bidirectional"))
    )
    (net (code "54") (name "Net-(D1-K)") (class "Default")
      (node (ref "D1") (pin "C") (pinfunction "K_C") (pintype "passive"))
      (node (ref "L1") (pin "1") (pinfunction "1_1") (pintype "bidirectional"))
      (node (ref "U17") (pin "3") (pinfunction "SW_3") (pintype "output"))
      (node (ref "U17") (pin "3.1") (pinfunction "SW_3.1") (pintype "output"))
    )
    (net (code "55") (name "Net-(LED7-PadC)") (class "Default")
      (node (ref "LED7") (pin "C") (pinfunction "C_C") (pintype "passive"))
      (node (ref "R13") (pin "2") (pinfunction "2_2") (pintype "passive"))
    )
    (net (code "56") (name "Net-(SG1-2)") (class "Default")
      (node (ref "R9") (pin "2") (pinfunction "2_2") (pintype "passive"))
      (node (ref "SG1") (pin "-") (pinfunction "2_-") (pintype "passive"))
    )
    (net (code "57") (name "Net-(U17-VC)") (class "Default")
      (node (ref "C13") (pin "2") (pinfunction "2_2") (pintype "passive"))
      (node (ref "U17") (pin "4") (pinfunction "VC_4") (pintype "passive"))
    )
    (net (code "58") (name "RXS") (class "Default")
      (node (ref "JP10") (pin "1") (pinfunction "1_1") (pintype "passive"))
      (node (ref "U$22") (pin "P$1") (pinfunction "1_P$1") (pintype "bidirectional"))
    )
    (net (code "59") (name "TXS") (class "Default")
      (node (ref "JP11") (pin "1") (pinfunction "1_1") (pintype "passive"))
      (node (ref "U$22") (pin "P$2") (pinfunction "2_P$2") (pintype "bidirectional"))
    )
    (net (code "60") (name "unconnected-(U$1-AN_IN2+-Pad22)") (class "Default")
      (node (ref "U$1") (pin "22") (pinfunction "AN_IN2+_22") (pintype "bidirectional"))
    )
    (net (code "61") (name "unconnected-(U$1-AN_IN2--Pad21)") (class "Default")
      (node (ref "U$1") (pin "21") (pinfunction "AN_IN2-_21") (pintype "bidirectional"))
    )
    (net (code "62") (name "unconnected-(U$1-AN_OUT2-Pad19)") (class "Default")
      (node (ref "U$1") (pin "19") (pinfunction "AN_OUT2_19") (pintype "bidirectional"))
    )
    (net (code "63") (name "unconnected-(U$1-DIG_IN1-Pad17)") (class "Default")
      (node (ref "U$1") (pin "17") (pinfunction "DIG_IN1_17") (pintype "bidirectional"))
    )
    (net (code "64") (name "unconnected-(U$1-DIG_IN2-Pad16)") (class "Default")
      (node (ref "U$1") (pin "16") (pinfunction "DIG_IN2_16") (pintype "bidirectional"))
    )
    (net (code "65") (name "unconnected-(U$2-LOG_V-PadLOG_VCC)") (class "Default")
      (node (ref "U$2") (pin "LOG_VCC") (pinfunction "LOG_V_LOG_VCC") (pintype "bidirectional"))
    )
    (net (code "66") (name "unconnected-(U$2-Pad18)") (class "Default")
      (node (ref "U$2") (pin "18") (pinfunction "18_18") (pintype "bidirectional"))
    )
    (net (code "67") (name "unconnected-(U$2-PadRX)") (class "Default")
      (node (ref "U$2") (pin "RX") (pinfunction "RX_RX") (pintype "bidirectional"))
    )
    (net (code "68") (name "unconnected-(U$2-PadSCL)") (class "Default")
      (node (ref "U$2") (pin "SCL") (pinfunction "SCL_SCL") (pintype "bidirectional"))
    )
    (net (code "69") (name "unconnected-(U$2-PadSDA)") (class "Default")
      (node (ref "U$2") (pin "SDA") (pinfunction "SDA_SDA") (pintype "bidirectional"))
    )
    (net (code "70") (name "unconnected-(U$2-PadTX)") (class "Default")
      (node (ref "U$2") (pin "TX") (pinfunction "TX_TX") (pintype "bidirectional"))
    )
    (net (code "71") (name "unconnected-(U$2-PadVCC)") (class "Default")
      (node (ref "U$2") (pin "VCC") (pinfunction "VCC_VCC") (pintype "bidirectional"))
    )
    (net (code "72") (name "unconnected-(U$3-PSO-PadPS0)") (class "Default")
      (node (ref "U$3") (pin "PS0") (pinfunction "PSO_PS0") (pintype "bidirectional"))
    )
    (net (code "73") (name "unconnected-(U$3-Pad3VO)") (class "Default")
      (node (ref "U$3") (pin "3VO") (pinfunction "3VO_3VO") (pintype "bidirectional"))
    )
    (net (code "74") (name "unconnected-(U$3-PadADR)") (class "Default")
      (node (ref "U$3") (pin "ADR") (pinfunction "ADR_ADR") (pintype "bidirectional"))
    )
    (net (code "75") (name "unconnected-(U$3-PadINT)") (class "Default")
      (node (ref "U$3") (pin "INT") (pinfunction "INT_INT") (pintype "bidirectional"))
    )
    (net (code "76") (name "unconnected-(U$3-PadRST)") (class "Default")
      (node (ref "U$3") (pin "RST") (pinfunction "RST_RST") (pintype "bidirectional"))
    )
    (net (code "77") (name "unconnected-(U$5-1-PadA1)") (class "Default")
      (node (ref "U$5") (pin "A1") (pinfunction "1_A1") (pintype "bidirectional"))
    )
    (net (code "78") (name "unconnected-(U$5-4-PadA4)") (class "Default")
      (node (ref "U$5") (pin "A4") (pinfunction "4_A4") (pintype "bidirectional"))
    )
    (net (code "79") (name "unconnected-(U$5-9-PadA9)") (class "Default")
      (node (ref "U$5") (pin "A9") (pinfunction "9_A9") (pintype "bidirectional"))
    )
    (net (code "80") (name "unconnected-(U$5-10-PadA10)") (class "Default")
      (node (ref "U$5") (pin "A10") (pinfunction "10_A10") (pintype "bidirectional"))
    )
    (net (code "81") (name "unconnected-(U$6-6-PadB6)") (class "Default")
      (node (ref "U$6") (pin "B6") (pinfunction "6_B6") (pintype "bidirectional"))
    )
    (net (code "82") (name "unconnected-(U$7-4-PadC4)") (class "Default")
      (node (ref "U$7") (pin "C4") (pinfunction "4_C4") (pintype "bidirectional"))
    )
    (net (code "83") (name "unconnected-(U$10-AN_IN2+-Pad22)") (class "Default")
      (node (ref "U$10") (pin "22") (pinfunction "AN_IN2+_22") (pintype "bidirectional"))
    )
    (net (code "84") (name "unconnected-(U$10-AN_IN2--Pad21)") (class "Default")
      (node (ref "U$10") (pin "21") (pinfunction "AN_IN2-_21") (pintype "bidirectional"))
    )
    (net (code "85") (name "unconnected-(U$10-AN_OUT1-Pad20)") (class "Default")
      (node (ref "U$10") (pin "20") (pinfunction "AN_OUT1_20") (pintype "bidirectional"))
    )
    (net (code "86") (name "unconnected-(U$10-AN_OUT2-Pad19)") (class "Default")
      (node (ref "U$10") (pin "19") (pinfunction "AN_OUT2_19") (pintype "bidirectional"))
    )
    (net (code "87") (name "unconnected-(U$10-DIG_IN1-Pad17)") (class "Default")
      (node (ref "U$10") (pin "17") (pinfunction "DIG_IN1_17") (pintype "bidirectional"))
    )
    (net (code "88") (name "unconnected-(U$10-DIG_IN2-Pad16)") (class "Default")
      (node (ref "U$10") (pin "16") (pinfunction "DIG_IN2_16") (pintype "bidirectional"))
    )
    (net (code "89") (name "unconnected-(U$10-ENCODER_CHA-Pad10)") (class "Default")
      (node (ref "U$10") (pin "10") (pinfunction "ENCODER_CHA_10") (pintype "bidirectional"))
    )
    (net (code "90") (name "unconnected-(U$10-ENCODER_CHA\\\\-Pad11)") (class "Default")
      (node (ref "U$10") (pin "11") (pinfunction "ENCODER_CHA\\\\_11") (pintype "bidirectional"))
    )
    (net (code "91") (name "unconnected-(U$10-ENCODER_CHB-Pad12)") (class "Default")
      (node (ref "U$10") (pin "12") (pinfunction "ENCODER_CHB_12") (pintype "bidirectional"))
    )
    (net (code "92") (name "unconnected-(U$10-ENCODER_CHB\\\\-Pad13)") (class "Default")
      (node (ref "U$10") (pin "13") (pinfunction "ENCODER_CHB\\\\_13") (pintype "bidirectional"))
    )
    (net (code "93") (name "unconnected-(U$13-4-PadP$4)") (class "Default")
      (node (ref "U$13") (pin "P$4") (pinfunction "4_P$4") (pintype "bidirectional"))
    )
    (net (code "94") (name "unconnected-(U$14-1-PadP$10)") (class "Default")
      (node (ref "U$14") (pin "P$10") (pinfunction "1_P$10") (pintype "bidirectional"))
    )
    (net (code "95") (name "unconnected-(U$14-10-PadP$1)") (class "Default")
      (node (ref "U$14") (pin "P$1") (pinfunction "10_P$1") (pintype "bidirectional"))
    )
    (net (code "96") (name "unconnected-(U$15-AN_IN2+-Pad22)") (class "Default")
      (node (ref "U$15") (pin "22") (pinfunction "AN_IN2+_22") (pintype "bidirectional"))
    )
    (net (code "97") (name "unconnected-(U$15-AN_IN2--Pad21)") (class "Default")
      (node (ref "U$15") (pin "21") (pinfunction "AN_IN2-_21") (pintype "bidirectional"))
    )
    (net (code "98") (name "unconnected-(U$15-AN_OUT2-Pad19)") (class "Default")
      (node (ref "U$15") (pin "19") (pinfunction "AN_OUT2_19") (pintype "bidirectional"))
    )
    (net (code "99") (name "unconnected-(U$15-DIG_IN1-Pad17)") (class "Default")
      (node (ref "U$15") (pin "17") (pinfunction "DIG_IN1_17") (pintype "bidirectional"))
    )
    (net (code "100") (name "unconnected-(U$15-DIG_IN2-Pad16)") (class "Default")
      (node (ref "U$15") (pin "16") (pinfunction "DIG_IN2_16") (pintype "bidirectional"))
    )
    (net (code "101") (name "unconnected-(U$17-1-PadA1)") (class "Default")
      (node (ref "U$17") (pin "A1") (pinfunction "1_A1") (pintype "bidirectional"))
    )
    (net (code "102") (name "unconnected-(U$17-4-PadA4)") (class "Default")
      (node (ref "U$17") (pin "A4") (pinfunction "4_A4") (pintype "bidirectional"))
    )
    (net (code "103") (name "unconnected-(U$17-9-PadA9)") (class "Default")
      (node (ref "U$17") (pin "A9") (pinfunction "9_A9") (pintype "bidirectional"))
    )
    (net (code "104") (name "unconnected-(U$17-10-PadA10)") (class "Default")
      (node (ref "U$17") (pin "A10") (pinfunction "10_A10") (pintype "bidirectional"))
    )
    (net (code "105") (name "unconnected-(U$18-6-PadB6)") (class "Default")
      (node (ref "U$18") (pin "B6") (pinfunction "6_B6") (pintype "bidirectional"))
    )
    (net (code "106") (name "unconnected-(U$19-4-PadC4)") (class "Default")
      (node (ref "U$19") (pin "C4") (pinfunction "4_C4") (pintype "bidirectional"))
    )
  )
)
